# 48-24_0524.net
KiCad netlist of a schematic drawn in EasyEDA Pro
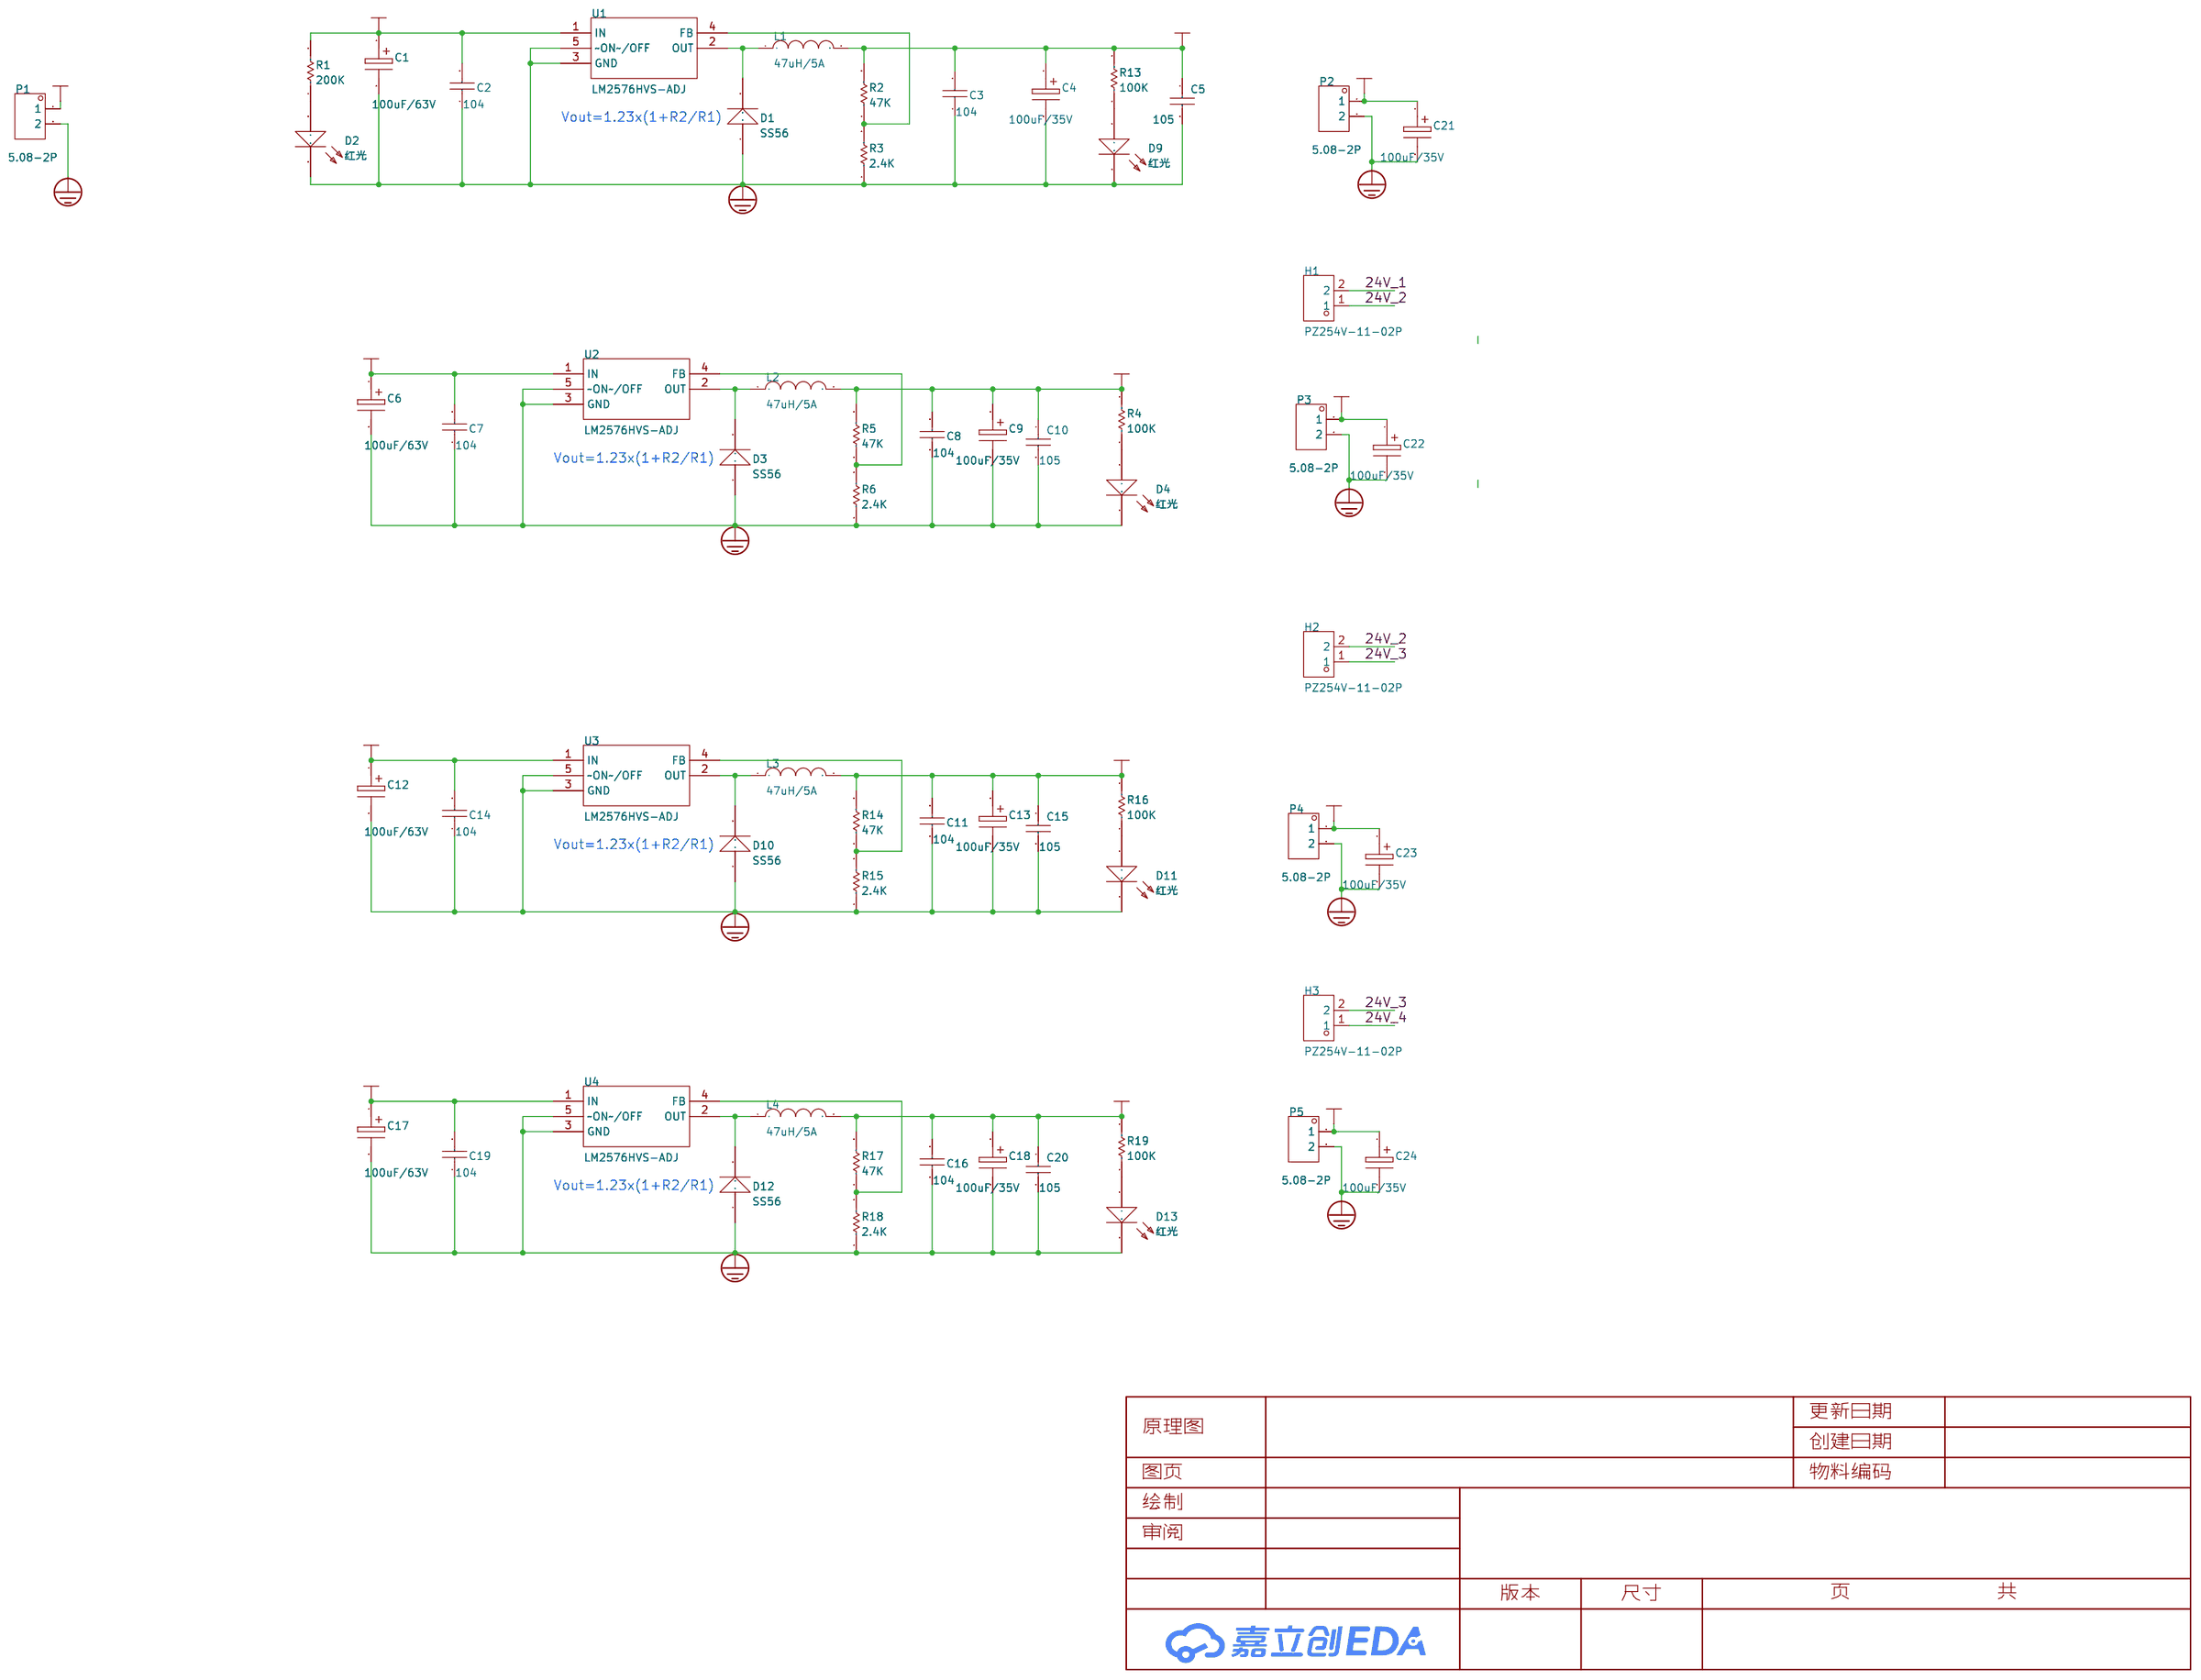
[diagram p0: schematic sheet]

(export (version "E")
  (design (tool "Eeschema 10.0.6"))
  (components
    (comp (ref "C1")
      (value "100uF/63V")
      (footprint "easyedapro:电解电容贴片10x10")
      (libsource (lib "easyedapro") (part "ELECTRO1"))
    )
    (comp (ref "C2")
      (value "104")
      (footprint "easyedapro:电解电容贴片6X6")
      (libsource (lib "easyedapro") (part "CAP"))
    )
    (comp (ref "C3")
      (value "104")
      (footprint "easyedapro:电解电容贴片6X6")
      (libsource (lib "easyedapro") (part "CAP"))
    )
    (comp (ref "C4")
      (value "100uF/35V")
      (footprint "easyedapro:电解电容贴片10x10")
      (libsource (lib "easyedapro") (part "ELECTRO1"))
    )
    (comp (ref "C5")
      (value "105")
      (footprint "easyedapro:电解电容贴片6X6")
      (libsource (lib "easyedapro") (part "CAP"))
    )
    (comp (ref "C6")
      (value "100uF/63V")
      (footprint "easyedapro:电解电容贴片10x10")
      (libsource (lib "easyedapro") (part "ELECTRO1"))
    )
    (comp (ref "C7")
      (value "104")
      (footprint "easyedapro:电解电容贴片6X6")
      (libsource (lib "easyedapro") (part "CAP"))
    )
    (comp (ref "C8")
      (value "104")
      (footprint "easyedapro:电解电容贴片6X6")
      (libsource (lib "easyedapro") (part "CAP"))
    )
    (comp (ref "C9")
      (value "100uF/35V")
      (footprint "easyedapro:电解电容贴片10x10")
      (libsource (lib "easyedapro") (part "ELECTRO1"))
    )
    (comp (ref "C10")
      (value "105")
      (footprint "easyedapro:电解电容贴片6X6")
      (libsource (lib "easyedapro") (part "CAP"))
    )
    (comp (ref "C11")
      (value "104")
      (footprint "easyedapro:电解电容贴片6X6")
      (libsource (lib "easyedapro") (part "CAP"))
    )
    (comp (ref "C12")
      (value "100uF/63V")
      (footprint "easyedapro:电解电容贴片10x10")
      (libsource (lib "easyedapro") (part "ELECTRO1"))
    )
    (comp (ref "C13")
      (value "100uF/35V")
      (footprint "easyedapro:电解电容贴片10x10")
      (libsource (lib "easyedapro") (part "ELECTRO1"))
    )
    (comp (ref "C14")
      (value "104")
      (footprint "easyedapro:电解电容贴片6X6")
      (libsource (lib "easyedapro") (part "CAP"))
    )
    (comp (ref "C15")
      (value "105")
      (footprint "easyedapro:电解电容贴片6X6")
      (libsource (lib "easyedapro") (part "CAP"))
    )
    (comp (ref "C16")
      (value "104")
      (footprint "easyedapro:电解电容贴片6X6")
      (libsource (lib "easyedapro") (part "CAP"))
    )
    (comp (ref "C17")
      (value "100uF/63V")
      (footprint "easyedapro:电解电容贴片10x10")
      (libsource (lib "easyedapro") (part "ELECTRO1"))
    )
    (comp (ref "C18")
      (value "100uF/35V")
      (footprint "easyedapro:电解电容贴片10x10")
      (libsource (lib "easyedapro") (part "ELECTRO1"))
    )
    (comp (ref "C19")
      (value "104")
      (footprint "easyedapro:电解电容贴片6X6")
      (libsource (lib "easyedapro") (part "CAP"))
    )
    (comp (ref "C20")
      (value "105")
      (footprint "easyedapro:电解电容贴片6X6")
      (libsource (lib "easyedapro") (part "CAP"))
    )
    (comp (ref "C21")
      (value "100uF/35V")
      (footprint "easyedapro:电解电容贴片10x10")
      (libsource (lib "easyedapro") (part "ELECTRO1"))
    )
    (comp (ref "C22")
      (value "100uF/35V")
      (footprint "easyedapro:电解电容贴片10x10")
      (libsource (lib "easyedapro") (part "ELECTRO1"))
    )
    (comp (ref "C23")
      (value "100uF/35V")
      (footprint "easyedapro:电解电容贴片10x10")
      (libsource (lib "easyedapro") (part "ELECTRO1"))
    )
    (comp (ref "C24")
      (value "100uF/35V")
      (footprint "easyedapro:电解电容贴片10x10")
      (libsource (lib "easyedapro") (part "ELECTRO1"))
    )
    (comp (ref "D1")
      (value "SS56")
      (footprint "easyedapro:SMA")
      (libsource (lib "easyedapro") (part "1N4148"))
    )
    (comp (ref "D2")
      (value "红光")
      (footprint "easyedapro:0603LED")
      (libsource (lib "easyedapro") (part "LED"))
    )
    (comp (ref "D3")
      (value "SS56")
      (footprint "easyedapro:SMA")
      (libsource (lib "easyedapro") (part "1N4148"))
    )
    (comp (ref "D4")
      (value "红光")
      (footprint "easyedapro:0603LED")
      (libsource (lib "easyedapro") (part "LED"))
    )
    (comp (ref "D9")
      (value "红光")
      (footprint "easyedapro:0603LED")
      (libsource (lib "easyedapro") (part "LED"))
    )
    (comp (ref "D10")
      (value "SS56")
      (footprint "easyedapro:SMA")
      (libsource (lib "easyedapro") (part "1N4148"))
    )
    (comp (ref "D11")
      (value "红光")
      (footprint "easyedapro:0603LED")
      (libsource (lib "easyedapro") (part "LED"))
    )
    (comp (ref "D12")
      (value "SS56")
      (footprint "easyedapro:SMA")
      (libsource (lib "easyedapro") (part "1N4148"))
    )
    (comp (ref "D13")
      (value "红光")
      (footprint "easyedapro:0603LED")
      (libsource (lib "easyedapro") (part "LED"))
    )
    (comp (ref "H1")
      (value "PZ254V-11-02P")
      (footprint "easyedapro:HDR-TH_2P-P2.54-V-M")
      (fields (field (name "Manufacturer") "XFCN(兴飞)"))
      (libsource (lib "easyedapro") (part "PZ254V-11-02P"))
    )
    (comp (ref "H2")
      (value "PZ254V-11-02P")
      (footprint "easyedapro:HDR-TH_2P-P2.54-V-M")
      (fields (field (name "Manufacturer") "XFCN(兴飞)"))
      (libsource (lib "easyedapro") (part "PZ254V-11-02P"))
    )
    (comp (ref "H3")
      (value "PZ254V-11-02P")
      (footprint "easyedapro:HDR-TH_2P-P2.54-V-M")
      (fields (field (name "Manufacturer") "XFCN(兴飞)"))
      (libsource (lib "easyedapro") (part "PZ254V-11-02P"))
    )
    (comp (ref "L1")
      (value "47uH/5A")
      (footprint "easyedapro:IND-SMD_L13.45-W12.6")
      (description "Inductor")
      (libsource (lib "easyedapro") (part "Inductor"))
    )
    (comp (ref "L2")
      (value "47uH/5A")
      (footprint "easyedapro:IND-SMD_L13.45-W12.6")
      (description "Inductor")
      (libsource (lib "easyedapro") (part "Inductor"))
    )
    (comp (ref "L3")
      (value "47uH/5A")
      (footprint "easyedapro:IND-SMD_L13.45-W12.6")
      (description "Inductor")
      (libsource (lib "easyedapro") (part "Inductor"))
    )
    (comp (ref "L4")
      (value "47uH/5A")
      (footprint "easyedapro:IND-SMD_L13.45-W12.6")
      (description "Inductor")
      (libsource (lib "easyedapro") (part "Inductor"))
    )
    (comp (ref "P1")
      (value "5.08-2P")
      (footprint "easyedapro:CONN-TH_WJ2EDGVC-5.08-2P")
      (fields (field (name "Manufacturer") "KANGNEX(康奈克斯电气)"))
      (libsource (lib "easyedapro") (part "WJ2EDGVC-5.08-2P"))
    )
    (comp (ref "P2")
      (value "5.08-2P")
      (footprint "easyedapro:CONN-TH_WJ2EDGVC-5.08-2P")
      (fields (field (name "Manufacturer") "KANGNEX(康奈克斯电气)"))
      (libsource (lib "easyedapro") (part "WJ2EDGVC-5.08-2P"))
    )
    (comp (ref "P3")
      (value "5.08-2P")
      (footprint "easyedapro:CONN-TH_WJ2EDGVC-5.08-2P")
      (fields (field (name "Manufacturer") "KANGNEX(康奈克斯电气)"))
      (libsource (lib "easyedapro") (part "WJ2EDGVC-5.08-2P"))
    )
    (comp (ref "P4")
      (value "5.08-2P")
      (footprint "easyedapro:CONN-TH_WJ2EDGVC-5.08-2P")
      (fields (field (name "Manufacturer") "KANGNEX(康奈克斯电气)"))
      (libsource (lib "easyedapro") (part "WJ2EDGVC-5.08-2P"))
    )
    (comp (ref "P5")
      (value "5.08-2P")
      (footprint "easyedapro:CONN-TH_WJ2EDGVC-5.08-2P")
      (fields (field (name "Manufacturer") "KANGNEX(康奈克斯电气)"))
      (libsource (lib "easyedapro") (part "WJ2EDGVC-5.08-2P"))
    )
    (comp (ref "R1")
      (value "10K")
      (footprint "easyedapro:0603R")
      (description "Resistor")
      (libsource (lib "easyedapro") (part "RES"))
    )
    (comp (ref "R2")
      (value "47K")
      (footprint "easyedapro:0603R")
      (description "Resistor")
      (libsource (lib "easyedapro") (part "RES"))
    )
    (comp (ref "R3")
      (value "2.4K")
      (footprint "easyedapro:0603R")
      (description "Resistor")
      (libsource (lib "easyedapro") (part "RES"))
    )
    (comp (ref "R4")
      (value "10K")
      (footprint "easyedapro:0603R")
      (description "Resistor")
      (libsource (lib "easyedapro") (part "RES"))
    )
    (comp (ref "R5")
      (value "47K")
      (footprint "easyedapro:0603R")
      (description "Resistor")
      (libsource (lib "easyedapro") (part "RES"))
    )
    (comp (ref "R6")
      (value "2.4K")
      (footprint "easyedapro:0603R")
      (description "Resistor")
      (libsource (lib "easyedapro") (part "RES"))
    )
    (comp (ref "R13")
      (value "10K")
      (footprint "easyedapro:0603R")
      (description "Resistor")
      (libsource (lib "easyedapro") (part "RES"))
    )
    (comp (ref "R14")
      (value "47K")
      (footprint "easyedapro:0603R")
      (description "Resistor")
      (libsource (lib "easyedapro") (part "RES"))
    )
    (comp (ref "R15")
      (value "2.4K")
      (footprint "easyedapro:0603R")
      (description "Resistor")
      (libsource (lib "easyedapro") (part "RES"))
    )
    (comp (ref "R16")
      (value "10K")
      (footprint "easyedapro:0603R")
      (description "Resistor")
      (libsource (lib "easyedapro") (part "RES"))
    )
    (comp (ref "R17")
      (value "47K")
      (footprint "easyedapro:0603R")
      (description "Resistor")
      (libsource (lib "easyedapro") (part "RES"))
    )
    (comp (ref "R18")
      (value "2.4K")
      (footprint "easyedapro:0603R")
      (description "Resistor")
      (libsource (lib "easyedapro") (part "RES"))
    )
    (comp (ref "R19")
      (value "10K")
      (footprint "easyedapro:0603R")
      (description "Resistor")
      (libsource (lib "easyedapro") (part "RES"))
    )
    (comp (ref "U1")
      (value "LM2576HVS-ADJ")
      (footprint "easyedapro:TO-263")
      (description "Simple Switcher 3A Step Down Voltage Regulator")
      (libsource (lib "easyedapro") (part "LM2576S-5.0"))
    )
    (comp (ref "U2")
      (value "LM2576HVS-ADJ")
      (footprint "easyedapro:TO-263")
      (description "Simple Switcher 3A Step Down Voltage Regulator")
      (libsource (lib "easyedapro") (part "LM2576S-5.0"))
    )
    (comp (ref "U3")
      (value "LM2576HVS-ADJ")
      (footprint "easyedapro:TO-263")
      (description "Simple Switcher 3A Step Down Voltage Regulator")
      (libsource (lib "easyedapro") (part "LM2576S-5.0"))
    )
    (comp (ref "U4")
      (value "LM2576HVS-ADJ")
      (footprint "easyedapro:TO-263")
      (description "Simple Switcher 3A Step Down Voltage Regulator")
      (libsource (lib "easyedapro") (part "LM2576S-5.0"))
    )
  )
  (nets
    (net (code "1") (name "24V_1") (class "Default")
      (node (ref "C21") (pin "1") (pintype "unspecified"))
      (node (ref "C3") (pin "2") (pinfunction "2_2") (pintype "unspecified"))
      (node (ref "C4") (pin "1") (pintype "unspecified"))
      (node (ref "C5") (pin "1") (pinfunction "1_1") (pintype "unspecified"))
      (node (ref "H1") (pin "2") (pinfunction "2_2") (pintype "unspecified"))
      (node (ref "L1") (pin "2") (pinfunction "2_2") (pintype "unspecified"))
      (node (ref "P2") (pin "1") (pinfunction "1_1") (pintype "unspecified"))
      (node (ref "R13") (pin "2") (pinfunction "2_2") (pintype "unspecified"))
      (node (ref "R2") (pin "2") (pinfunction "2_2") (pintype "unspecified"))
    )
    (net (code "2") (name "24V_2") (class "Default")
      (node (ref "C10") (pin "1") (pinfunction "1_1") (pintype "unspecified"))
      (node (ref "C22") (pin "1") (pintype "unspecified"))
      (node (ref "C8") (pin "2") (pinfunction "2_2") (pintype "unspecified"))
      (node (ref "C9") (pin "1") (pintype "unspecified"))
      (node (ref "H1") (pin "1") (pinfunction "1_1") (pintype "unspecified"))
      (node (ref "H2") (pin "2") (pinfunction "2_2") (pintype "unspecified"))
      (node (ref "L2") (pin "2") (pinfunction "2_2") (pintype "unspecified"))
      (node (ref "P3") (pin "1") (pinfunction "1_1") (pintype "unspecified"))
      (node (ref "R4") (pin "2") (pinfunction "2_2") (pintype "unspecified"))
      (node (ref "R5") (pin "2") (pinfunction "2_2") (pintype "unspecified"))
    )
    (net (code "3") (name "24V_3") (class "Default")
      (node (ref "C11") (pin "2") (pinfunction "2_2") (pintype "unspecified"))
      (node (ref "C13") (pin "1") (pintype "unspecified"))
      (node (ref "C15") (pin "1") (pinfunction "1_1") (pintype "unspecified"))
      (node (ref "C23") (pin "1") (pintype "unspecified"))
      (node (ref "H2") (pin "1") (pinfunction "1_1") (pintype "unspecified"))
      (node (ref "H3") (pin "2") (pinfunction "2_2") (pintype "unspecified"))
      (node (ref "L3") (pin "2") (pinfunction "2_2") (pintype "unspecified"))
      (node (ref "P4") (pin "1") (pinfunction "1_1") (pintype "unspecified"))
      (node (ref "R14") (pin "2") (pinfunction "2_2") (pintype "unspecified"))
      (node (ref "R16") (pin "2") (pinfunction "2_2") (pintype "unspecified"))
    )
    (net (code "4") (name "24V_4") (class "Default")
      (node (ref "C16") (pin "2") (pinfunction "2_2") (pintype "unspecified"))
      (node (ref "C18") (pin "1") (pintype "unspecified"))
      (node (ref "C20") (pin "1") (pinfunction "1_1") (pintype "unspecified"))
      (node (ref "C24") (pin "1") (pintype "unspecified"))
      (node (ref "H3") (pin "1") (pinfunction "1_1") (pintype "unspecified"))
      (node (ref "L4") (pin "2") (pinfunction "2_2") (pintype "unspecified"))
      (node (ref "P5") (pin "1") (pinfunction "1_1") (pintype "unspecified"))
      (node (ref "R17") (pin "2") (pinfunction "2_2") (pintype "unspecified"))
      (node (ref "R19") (pin "2") (pinfunction "2_2") (pintype "unspecified"))
    )
    (net (code "5") (name "48V_IN") (class "Default")
      (node (ref "C1") (pin "1") (pintype "unspecified"))
      (node (ref "C12") (pin "1") (pintype "unspecified"))
      (node (ref "C14") (pin "2") (pinfunction "2_2") (pintype "unspecified"))
      (node (ref "C17") (pin "1") (pintype "unspecified"))
      (node (ref "C19") (pin "2") (pinfunction "2_2") (pintype "unspecified"))
      (node (ref "C2") (pin "2") (pinfunction "2_2") (pintype "unspecified"))
      (node (ref "C6") (pin "1") (pintype "unspecified"))
      (node (ref "C7") (pin "2") (pinfunction "2_2") (pintype "unspecified"))
      (node (ref "P1") (pin "1") (pinfunction "1_1") (pintype "unspecified"))
      (node (ref "R1") (pin "2") (pinfunction "2_2") (pintype "unspecified"))
      (node (ref "U1") (pin "1") (pinfunction "IN_1") (pintype "unspecified"))
      (node (ref "U2") (pin "1") (pinfunction "IN_1") (pintype "unspecified"))
      (node (ref "U3") (pin "1") (pinfunction "IN_1") (pintype "unspecified"))
      (node (ref "U4") (pin "1") (pinfunction "IN_1") (pintype "unspecified"))
    )
    (net (code "6") (name "GND") (class "Default")
      (node (ref "C1") (pin "2") (pintype "unspecified"))
      (node (ref "C10") (pin "2") (pinfunction "2_2") (pintype "unspecified"))
      (node (ref "C11") (pin "1") (pinfunction "1_1") (pintype "unspecified"))
      (node (ref "C12") (pin "2") (pintype "unspecified"))
      (node (ref "C13") (pin "2") (pintype "unspecified"))
      (node (ref "C14") (pin "1") (pinfunction "1_1") (pintype "unspecified"))
      (node (ref "C15") (pin "2") (pinfunction "2_2") (pintype "unspecified"))
      (node (ref "C16") (pin "1") (pinfunction "1_1") (pintype "unspecified"))
      (node (ref "C17") (pin "2") (pintype "unspecified"))
      (node (ref "C18") (pin "2") (pintype "unspecified"))
      (node (ref "C19") (pin "1") (pinfunction "1_1") (pintype "unspecified"))
      (node (ref "C2") (pin "1") (pinfunction "1_1") (pintype "unspecified"))
      (node (ref "C20") (pin "2") (pinfunction "2_2") (pintype "unspecified"))
      (node (ref "C21") (pin "2") (pintype "unspecified"))
      (node (ref "C22") (pin "2") (pintype "unspecified"))
      (node (ref "C23") (pin "2") (pintype "unspecified"))
      (node (ref "C24") (pin "2") (pintype "unspecified"))
      (node (ref "C3") (pin "1") (pinfunction "1_1") (pintype "unspecified"))
      (node (ref "C4") (pin "2") (pintype "unspecified"))
      (node (ref "C5") (pin "2") (pinfunction "2_2") (pintype "unspecified"))
      (node (ref "C6") (pin "2") (pintype "unspecified"))
      (node (ref "C7") (pin "1") (pinfunction "1_1") (pintype "unspecified"))
      (node (ref "C8") (pin "1") (pinfunction "1_1") (pintype "unspecified"))
      (node (ref "C9") (pin "2") (pintype "unspecified"))
      (node (ref "D1") (pin "1") (pinfunction "1_1") (pintype "unspecified"))
      (node (ref "D10") (pin "1") (pinfunction "1_1") (pintype "unspecified"))
      (node (ref "D11") (pin "2") (pinfunction "2_2") (pintype "unspecified"))
      (node (ref "D12") (pin "1") (pinfunction "1_1") (pintype "unspecified"))
      (node (ref "D13") (pin "2") (pinfunction "2_2") (pintype "unspecified"))
      (node (ref "D2") (pin "2") (pinfunction "2_2") (pintype "unspecified"))
      (node (ref "D3") (pin "1") (pinfunction "1_1") (pintype "unspecified"))
      (node (ref "D4") (pin "2") (pinfunction "2_2") (pintype "unspecified"))
      (node (ref "D9") (pin "2") (pinfunction "2_2") (pintype "unspecified"))
      (node (ref "P1") (pin "2") (pinfunction "2_2") (pintype "unspecified"))
      (node (ref "P2") (pin "2") (pinfunction "2_2") (pintype "unspecified"))
      (node (ref "P3") (pin "2") (pinfunction "2_2") (pintype "unspecified"))
      (node (ref "P4") (pin "2") (pinfunction "2_2") (pintype "unspecified"))
      (node (ref "P5") (pin "2") (pinfunction "2_2") (pintype "unspecified"))
      (node (ref "R15") (pin "1") (pinfunction "1_1") (pintype "unspecified"))
      (node (ref "R18") (pin "1") (pinfunction "1_1") (pintype "unspecified"))
      (node (ref "R3") (pin "1") (pinfunction "1_1") (pintype "unspecified"))
      (node (ref "R6") (pin "1") (pinfunction "1_1") (pintype "unspecified"))
      (node (ref "U1") (pin "3") (pinfunction "GND_3") (pintype "unspecified"))
      (node (ref "U1") (pin "5") (pinfunction "~ON~/OFF_5") (pintype "input"))
      (node (ref "U2") (pin "3") (pinfunction "GND_3") (pintype "unspecified"))
      (node (ref "U2") (pin "5") (pinfunction "~ON~/OFF_5") (pintype "input"))
      (node (ref "U3") (pin "3") (pinfunction "GND_3") (pintype "unspecified"))
      (node (ref "U3") (pin "5") (pinfunction "~ON~/OFF_5") (pintype "input"))
      (node (ref "U4") (pin "3") (pinfunction "GND_3") (pintype "unspecified"))
      (node (ref "U4") (pin "5") (pinfunction "~ON~/OFF_5") (pintype "input"))
    )
    (net (code "7") (name "Net-(D2-Pad1)") (class "Default")
      (node (ref "D2") (pin "1") (pinfunction "1_1") (pintype "unspecified"))
      (node (ref "R1") (pin "1") (pinfunction "1_1") (pintype "unspecified"))
    )
    (net (code "8") (name "Net-(D4-Pad1)") (class "Default")
      (node (ref "D4") (pin "1") (pinfunction "1_1") (pintype "unspecified"))
      (node (ref "R4") (pin "1") (pinfunction "1_1") (pintype "unspecified"))
    )
    (net (code "9") (name "Net-(D9-Pad1)") (class "Default")
      (node (ref "D9") (pin "1") (pinfunction "1_1") (pintype "unspecified"))
      (node (ref "R13") (pin "1") (pinfunction "1_1") (pintype "unspecified"))
    )
    (net (code "10") (name "Net-(D11-Pad1)") (class "Default")
      (node (ref "D11") (pin "1") (pinfunction "1_1") (pintype "unspecified"))
      (node (ref "R16") (pin "1") (pinfunction "1_1") (pintype "unspecified"))
    )
    (net (code "11") (name "Net-(D13-Pad1)") (class "Default")
      (node (ref "D13") (pin "1") (pinfunction "1_1") (pintype "unspecified"))
      (node (ref "R19") (pin "1") (pinfunction "1_1") (pintype "unspecified"))
    )
    (net (code "12") (name "Net-(U1-FB)") (class "Default")
      (node (ref "R2") (pin "1") (pinfunction "1_1") (pintype "unspecified"))
      (node (ref "R3") (pin "2") (pinfunction "2_2") (pintype "unspecified"))
      (node (ref "U1") (pin "4") (pinfunction "FB_4") (pintype "input"))
    )
    (net (code "13") (name "Net-(U1-OUT)") (class "Default")
      (node (ref "D1") (pin "2") (pinfunction "2_2") (pintype "unspecified"))
      (node (ref "L1") (pin "1") (pinfunction "1_1") (pintype "unspecified"))
      (node (ref "U1") (pin "2") (pinfunction "OUT_2") (pintype "unspecified"))
    )
    (net (code "14") (name "Net-(U2-FB)") (class "Default")
      (node (ref "R5") (pin "1") (pinfunction "1_1") (pintype "unspecified"))
      (node (ref "R6") (pin "2") (pinfunction "2_2") (pintype "unspecified"))
      (node (ref "U2") (pin "4") (pinfunction "FB_4") (pintype "input"))
    )
    (net (code "15") (name "Net-(U2-OUT)") (class "Default")
      (node (ref "D3") (pin "2") (pinfunction "2_2") (pintype "unspecified"))
      (node (ref "L2") (pin "1") (pinfunction "1_1") (pintype "unspecified"))
      (node (ref "U2") (pin "2") (pinfunction "OUT_2") (pintype "unspecified"))
    )
    (net (code "16") (name "Net-(U3-FB)") (class "Default")
      (node (ref "R14") (pin "1") (pinfunction "1_1") (pintype "unspecified"))
      (node (ref "R15") (pin "2") (pinfunction "2_2") (pintype "unspecified"))
      (node (ref "U3") (pin "4") (pinfunction "FB_4") (pintype "input"))
    )
    (net (code "17") (name "Net-(U3-OUT)") (class "Default")
      (node (ref "D10") (pin "2") (pinfunction "2_2") (pintype "unspecified"))
      (node (ref "L3") (pin "1") (pinfunction "1_1") (pintype "unspecified"))
      (node (ref "U3") (pin "2") (pinfunction "OUT_2") (pintype "unspecified"))
    )
    (net (code "18") (name "Net-(U4-FB)") (class "Default")
      (node (ref "R17") (pin "1") (pinfunction "1_1") (pintype "unspecified"))
      (node (ref "R18") (pin "2") (pinfunction "2_2") (pintype "unspecified"))
      (node (ref "U4") (pin "4") (pinfunction "FB_4") (pintype "input"))
    )
    (net (code "19") (name "Net-(U4-OUT)") (class "Default")
      (node (ref "D12") (pin "2") (pinfunction "2_2") (pintype "unspecified"))
      (node (ref "L4") (pin "1") (pinfunction "1_1") (pintype "unspecified"))
      (node (ref "U4") (pin "2") (pinfunction "OUT_2") (pintype "unspecified"))
    )
  )
)
